# 02_Power.net
KiCad netlist of a schematic drawn in Altium Designer
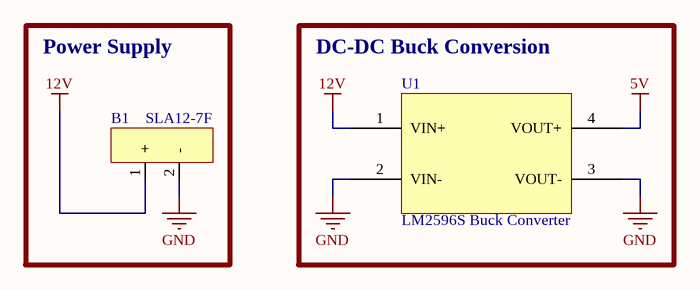
[diagram p0: 02_Power.SchDoc]

(export (version "E")
  (design (tool "Eeschema 10.0.6"))
  (components
    (comp (ref "B1")
      (value "SLA12-7F")
      (footprint "SLA12-7F")
      (fields (field (name "MANUFACTURER") "AJC") (field (name "MANUFACTURER PART NUMBER") "AJC-D7S"))
      (libsource (lib "Ground Support_Schlib") (part "SLA12-7F"))
    )
    (comp (ref "U1")
      (value "LM2596S Buck Converter")
      (footprint "LM2596S Buck Converter")
      (fields
        (field (name "MANUFACTURER") "Frienda")
        (field (name "MANUFACTURER PART NUMBER") "Frienda-Power Converters-01")
      )
      (libsource (lib "Ground Support_Schlib") (part "LM2596S Buck Converter"))
    )
  )
  (nets
    (net (code "1") (name "5V") (class "Default")
      (node (ref "U1") (pin "4") (pinfunction "VOUT+_4") (pintype "passive"))
    )
    (net (code "2") (name "12V") (class "Default")
      (node (ref "B1") (pin "1") (pinfunction "+_1") (pintype "power_in"))
      (node (ref "U1") (pin "1") (pinfunction "VIN+_1") (pintype "passive"))
    )
    (net (code "3") (name "GND") (class "Default")
      (node (ref "B1") (pin "2") (pinfunction "-_2") (pintype "power_in"))
      (node (ref "U1") (pin "2") (pinfunction "VIN-_2") (pintype "passive"))
      (node (ref "U1") (pin "3") (pinfunction "VOUT-_3") (pintype "passive"))
    )
  )
)
